# module.net
KiCad netlist of a schematic drawn in EAGLE
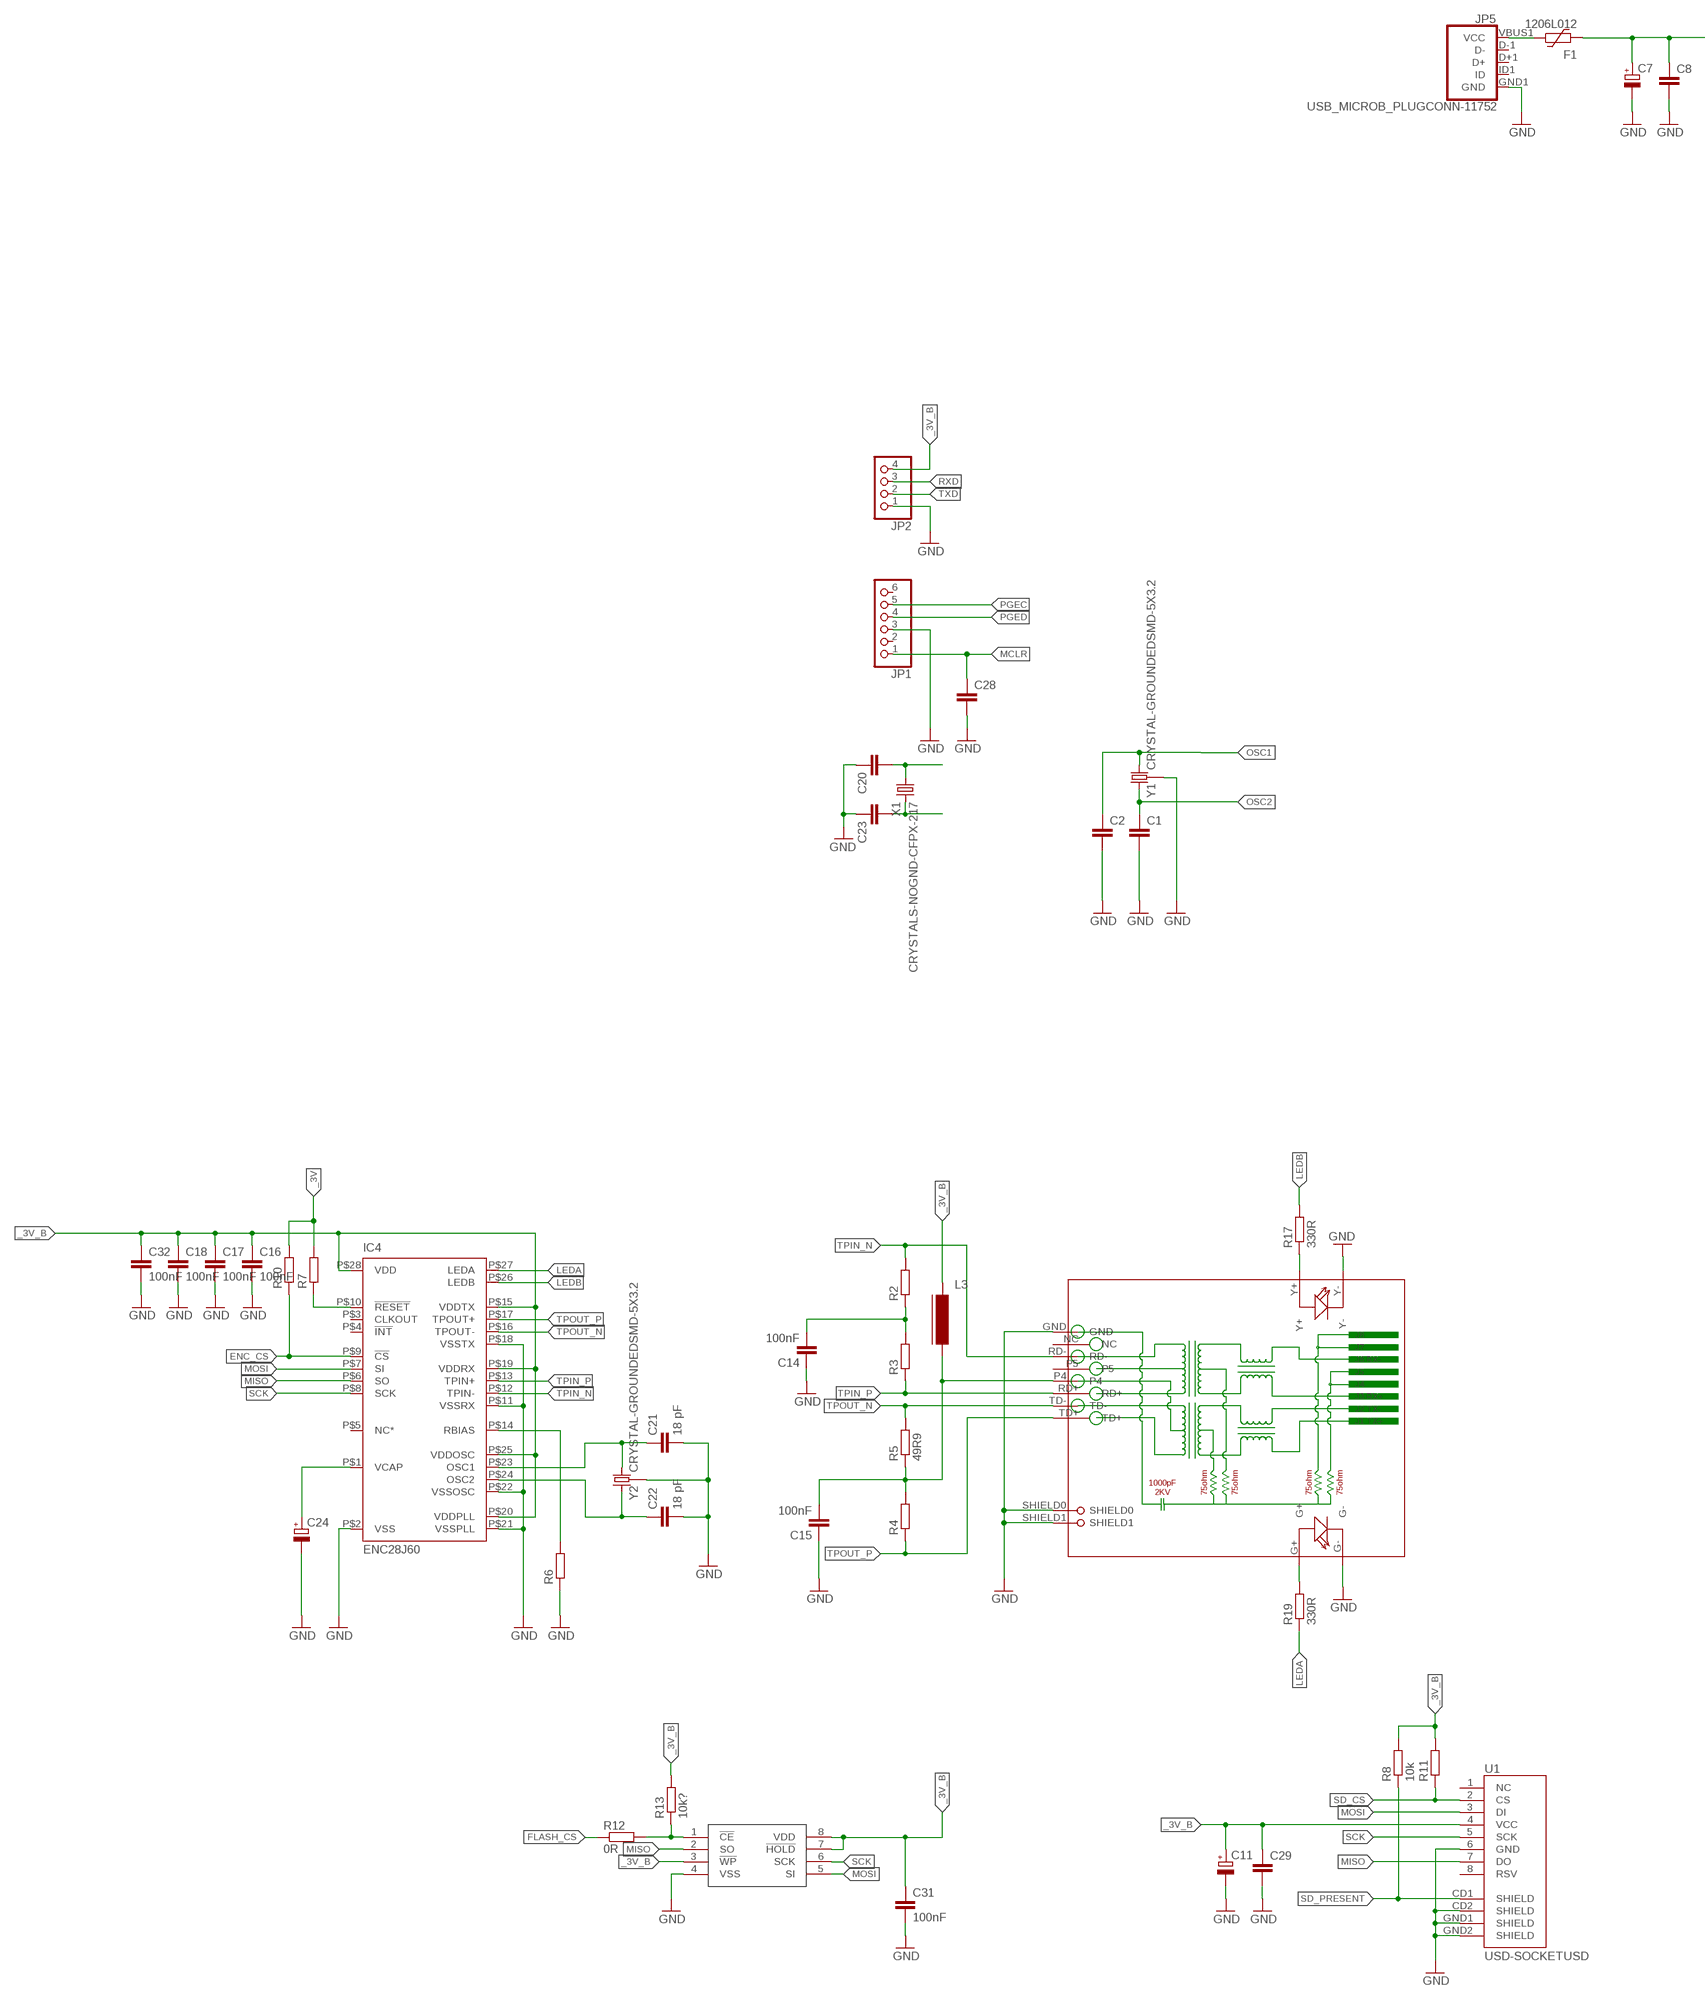
[diagram p0: schematic, sheet 1, part 1 of 2]
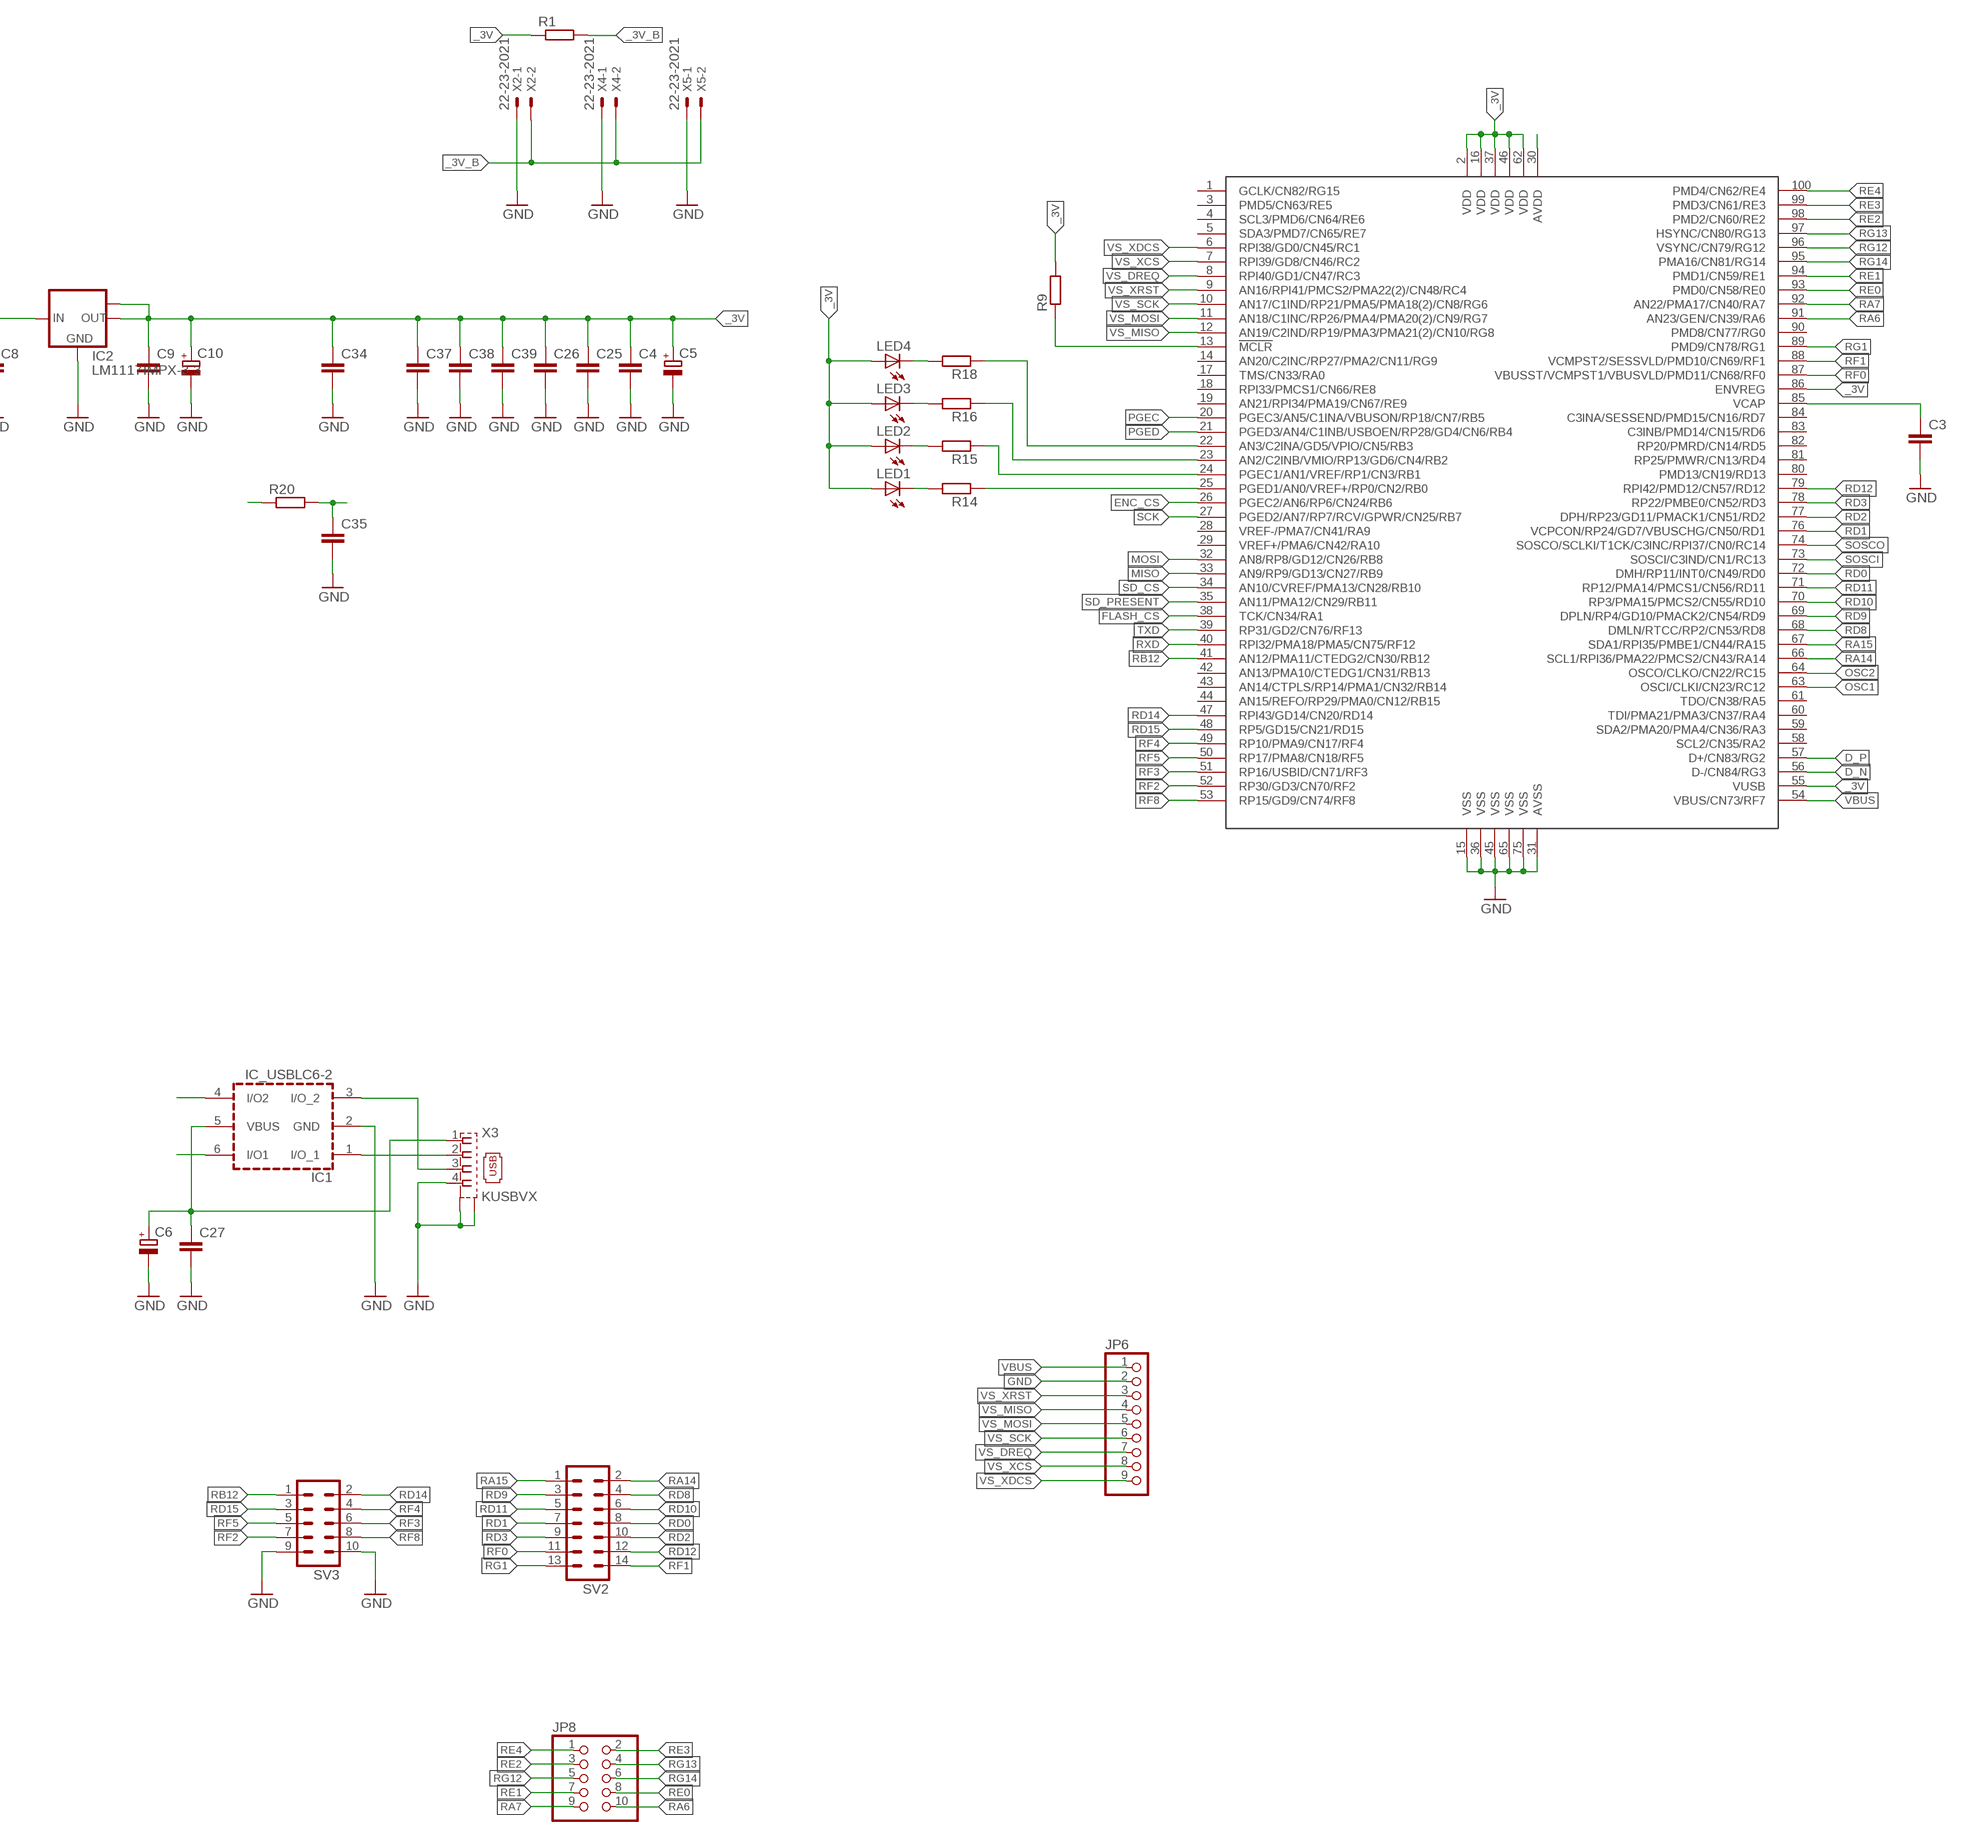
[diagram p1: schematic, sheet 1, part 2 of 2]

(export (version "E")
  (design (tool "Eeschema 10.0.6"))
  (components
    (comp (ref "C1")
      (value "C-EUC0603")
      (footprint "eagle-import:C0603")
      (libsource (lib "eagle-import") (part "C-EUC0603"))
    )
    (comp (ref "C2")
      (value "C-EUC0603")
      (footprint "eagle-import:C0603")
      (libsource (lib "eagle-import") (part "C-EUC0603"))
    )
    (comp (ref "C3")
      (value "C-EUC0603")
      (footprint "eagle-import:C0603")
      (libsource (lib "eagle-import") (part "C-EUC0603"))
    )
    (comp (ref "C4")
      (value "C-EUC0402")
      (footprint "eagle-import:C0402")
      (libsource (lib "eagle-import") (part "C-EUC0402"))
    )
    (comp (ref "C5")
      (value "CPOL-EUSMCA")
      (footprint "eagle-import:SMC_A")
      (libsource (lib "eagle-import") (part "CPOL-EUSMCA"))
    )
    (comp (ref "C6")
      (value "CPOL-EUSMCB")
      (footprint "eagle-import:SMC_B")
      (libsource (lib "eagle-import") (part "CPOL-EUSMCB"))
    )
    (comp (ref "C7")
      (value "CPOL-EUSMCB")
      (footprint "eagle-import:SMC_B")
      (libsource (lib "eagle-import") (part "CPOL-EUSMCB"))
    )
    (comp (ref "C8")
      (value "C-EUC0603")
      (footprint "eagle-import:C0603")
      (libsource (lib "eagle-import") (part "C-EUC0603"))
    )
    (comp (ref "C9")
      (value "C-EUC0603")
      (footprint "eagle-import:C0603")
      (libsource (lib "eagle-import") (part "C-EUC0603"))
    )
    (comp (ref "C10")
      (value "CPOL-EUSMCB")
      (footprint "eagle-import:SMC_B")
      (libsource (lib "eagle-import") (part "CPOL-EUSMCB"))
    )
    (comp (ref "C11")
      (value "CPOL-EUSMCA")
      (footprint "eagle-import:SMC_A")
      (libsource (lib "eagle-import") (part "CPOL-EUSMCA"))
    )
    (comp (ref "C14")
      (value "100nF")
      (footprint "eagle-import:C0603")
      (libsource (lib "eagle-import") (part "C-EUC0603"))
    )
    (comp (ref "C15")
      (value "100nF")
      (footprint "eagle-import:C0603")
      (libsource (lib "eagle-import") (part "C-EUC0603"))
    )
    (comp (ref "C16")
      (value "100nF")
      (footprint "eagle-import:C0402")
      (libsource (lib "eagle-import") (part "C-EUC0402"))
    )
    (comp (ref "C17")
      (value "100nF")
      (footprint "eagle-import:C0603")
      (libsource (lib "eagle-import") (part "C-EUC0603"))
    )
    (comp (ref "C18")
      (value "100nF")
      (footprint "eagle-import:C0603")
      (libsource (lib "eagle-import") (part "C-EUC0603"))
    )
    (comp (ref "C20")
      (value "C-EUC0603")
      (footprint "eagle-import:C0603")
      (libsource (lib "eagle-import") (part "C-EUC0603"))
    )
    (comp (ref "C21")
      (value "18 pF")
      (footprint "eagle-import:C0603")
      (libsource (lib "eagle-import") (part "C-EUC0603"))
    )
    (comp (ref "C22")
      (value "18 pF")
      (footprint "eagle-import:C0603")
      (libsource (lib "eagle-import") (part "C-EUC0603"))
    )
    (comp (ref "C23")
      (value "C-EUC0603")
      (footprint "eagle-import:C0603")
      (libsource (lib "eagle-import") (part "C-EUC0603"))
    )
    (comp (ref "C24")
      (value "CPOL-EUSMCA")
      (footprint "eagle-import:SMC_A")
      (libsource (lib "eagle-import") (part "CPOL-EUSMCA"))
    )
    (comp (ref "C25")
      (value "C-EUC0402")
      (footprint "eagle-import:C0402")
      (libsource (lib "eagle-import") (part "C-EUC0402"))
    )
    (comp (ref "C26")
      (value "C-EUC0402")
      (footprint "eagle-import:C0402")
      (libsource (lib "eagle-import") (part "C-EUC0402"))
    )
    (comp (ref "C27")
      (value "C-EUC0805")
      (footprint "eagle-import:C0805")
      (libsource (lib "eagle-import") (part "C-EUC0805"))
    )
    (comp (ref "C28")
      (value "C-EUC0603")
      (footprint "eagle-import:C0603")
      (libsource (lib "eagle-import") (part "C-EUC0603"))
    )
    (comp (ref "C29")
      (value "C-EUC0603")
      (footprint "eagle-import:C0603")
      (libsource (lib "eagle-import") (part "C-EUC0603"))
    )
    (comp (ref "C31")
      (value "100nF")
      (footprint "eagle-import:C0603")
      (libsource (lib "eagle-import") (part "C-EUC0603"))
    )
    (comp (ref "C32")
      (value "100nF")
      (footprint "eagle-import:C0402")
      (libsource (lib "eagle-import") (part "C-EUC0402"))
    )
    (comp (ref "C34")
      (value "C-EUC0402")
      (footprint "eagle-import:C0402")
      (libsource (lib "eagle-import") (part "C-EUC0402"))
    )
    (comp (ref "C35")
      (value "C-EUC0402")
      (footprint "eagle-import:C0402")
      (libsource (lib "eagle-import") (part "C-EUC0402"))
    )
    (comp (ref "C37")
      (value "C-EUC0402")
      (footprint "eagle-import:C0402")
      (libsource (lib "eagle-import") (part "C-EUC0402"))
    )
    (comp (ref "C38")
      (value "C-EUC0603")
      (footprint "eagle-import:C0603")
      (libsource (lib "eagle-import") (part "C-EUC0603"))
    )
    (comp (ref "C39")
      (value "C-EUC0402")
      (footprint "eagle-import:C0402")
      (libsource (lib "eagle-import") (part "C-EUC0402"))
    )
    (comp (ref "F1")
      (value "1206L012")
      (footprint "eagle-import:1206L")
      (fields (field (name "MF") "Littelfuse"))
      (libsource (lib "eagle-import") (part "?1206L012"))
    )
    (comp (ref "IC1")
      (value "IC_USBLC6-2")
      (footprint "eagle-import:SOT-23-6L")
      (libsource (lib "eagle-import") (part "IC_USBLC6-2"))
    )
    (comp (ref "IC2")
      (value "LM1117IMPX-3.3")
      (footprint "eagle-import:SOT223")
      (libsource (lib "eagle-import") (part "LM1117IMPX-3.3"))
    )
    (comp (ref "IC4")
      (value "ENC28J60")
      (footprint "eagle-import:TSSOP28W")
      (libsource (lib "eagle-import") (part "ENC28J60"))
    )
    (comp (ref "JP1")
      (value "PINHD-1X6")
      (footprint "eagle-import:1X06")
      (libsource (lib "eagle-import") (part "PINHD-1X6"))
    )
    (comp (ref "JP2")
      (value "PINHD-1X4")
      (footprint "eagle-import:1X04")
      (libsource (lib "eagle-import") (part "PINHD-1X4"))
    )
    (comp (ref "JP5")
      (value "USB_MICROB_PLUGCONN-11752")
      (footprint "eagle-import:USB-B-MICRO-SMD_V03")
      (libsource (lib "eagle-import") (part "USB_MICROB_PLUGCONN-11752"))
    )
    (comp (ref "JP6")
      (value "PINHD-1X9")
      (footprint "eagle-import:1X09")
      (libsource (lib "eagle-import") (part "PINHD-1X9"))
    )
    (comp (ref "JP8")
      (value "PINHD-2X5")
      (footprint "eagle-import:2X05")
      (libsource (lib "eagle-import") (part "PINHD-2X5"))
    )
    (comp (ref "L3")
      (value "FERRITE-0805")
      (footprint "eagle-import:FB805")
      (libsource (lib "eagle-import") (part "FERRITE-0805"))
    )
    (comp (ref "LED1")
      (value "LEDCHIP-LED0603")
      (footprint "eagle-import:CHIP-LED0603")
      (libsource (lib "eagle-import") (part "LEDCHIP-LED0603"))
    )
    (comp (ref "LED2")
      (value "LEDCHIP-LED0603")
      (footprint "eagle-import:CHIP-LED0603")
      (libsource (lib "eagle-import") (part "LEDCHIP-LED0603"))
    )
    (comp (ref "LED3")
      (value "LEDCHIP-LED0603")
      (footprint "eagle-import:CHIP-LED0603")
      (libsource (lib "eagle-import") (part "LEDCHIP-LED0603"))
    )
    (comp (ref "LED4")
      (value "LEDCHIP-LED0603")
      (footprint "eagle-import:CHIP-LED0603")
      (libsource (lib "eagle-import") (part "LEDCHIP-LED0603"))
    )
    (comp (ref "R1")
      (value "R-EU_R2010")
      (footprint "eagle-import:R2010")
      (libsource (lib "eagle-import") (part "R-EU_R2010"))
    )
    (comp (ref "R2")
      (value "R-EU_R0603")
      (footprint "eagle-import:R0603")
      (libsource (lib "eagle-import") (part "R-EU_R0603"))
    )
    (comp (ref "R3")
      (value "R-EU_R0603")
      (footprint "eagle-import:R0603")
      (libsource (lib "eagle-import") (part "R-EU_R0603"))
    )
    (comp (ref "R4")
      (value "R-EU_R0603")
      (footprint "eagle-import:R0603")
      (libsource (lib "eagle-import") (part "R-EU_R0603"))
    )
    (comp (ref "R5")
      (value "49R9")
      (footprint "eagle-import:R0603")
      (libsource (lib "eagle-import") (part "R-EU_R0603"))
    )
    (comp (ref "R6")
      (value "R-EU_R0805")
      (footprint "eagle-import:R0805")
      (libsource (lib "eagle-import") (part "R-EU_R0805"))
    )
    (comp (ref "R7")
      (value "R-EU_R0603")
      (footprint "eagle-import:R0603")
      (libsource (lib "eagle-import") (part "R-EU_R0603"))
    )
    (comp (ref "R8")
      (value "10k")
      (footprint "eagle-import:R0603")
      (libsource (lib "eagle-import") (part "R-EU_R0603"))
    )
    (comp (ref "R9")
      (value "R-EU_R0603")
      (footprint "eagle-import:R0603")
      (libsource (lib "eagle-import") (part "R-EU_R0603"))
    )
    (comp (ref "R10")
      (value "R-EU_R0603")
      (footprint "eagle-import:R0603")
      (libsource (lib "eagle-import") (part "R-EU_R0603"))
    )
    (comp (ref "R11")
      (value "R-EU_R0603")
      (footprint "eagle-import:R0603")
      (libsource (lib "eagle-import") (part "R-EU_R0603"))
    )
    (comp (ref "R12")
      (value "0R")
      (footprint "eagle-import:R0603")
      (libsource (lib "eagle-import") (part "R-EU_R0603"))
    )
    (comp (ref "R13")
      (value "10k?")
      (footprint "eagle-import:R0603")
      (libsource (lib "eagle-import") (part "R-EU_R0603"))
    )
    (comp (ref "R14")
      (value "R-EU_R0603")
      (footprint "eagle-import:R0603")
      (libsource (lib "eagle-import") (part "R-EU_R0603"))
    )
    (comp (ref "R15")
      (value "R-EU_R0603")
      (footprint "eagle-import:R0603")
      (libsource (lib "eagle-import") (part "R-EU_R0603"))
    )
    (comp (ref "R16")
      (value "R-EU_R0603")
      (footprint "eagle-import:R0603")
      (libsource (lib "eagle-import") (part "R-EU_R0603"))
    )
    (comp (ref "R17")
      (value "330R")
      (footprint "eagle-import:R1206")
      (libsource (lib "eagle-import") (part "R-EU_R1206"))
    )
    (comp (ref "R18")
      (value "R-EU_R0603")
      (footprint "eagle-import:R0603")
      (libsource (lib "eagle-import") (part "R-EU_R0603"))
    )
    (comp (ref "R19")
      (value "330R")
      (footprint "eagle-import:R1206")
      (libsource (lib "eagle-import") (part "R-EU_R1206"))
    )
    (comp (ref "R20")
      (value "R-EU_R0805")
      (footprint "eagle-import:R0805")
      (libsource (lib "eagle-import") (part "R-EU_R0805"))
    )
    (comp (ref "RJ1")
      (value "HR911105A")
      (footprint "eagle-import:HR911105A")
      (libsource (lib "eagle-import") (part "HR911105A"))
    )
    (comp (ref "SV2")
      (value "ML14L")
      (footprint "eagle-import:ML14L")
      (libsource (lib "eagle-import") (part "ML14L"))
    )
    (comp (ref "SV3")
      (value "ML10L")
      (footprint "eagle-import:ML10L")
      (libsource (lib "eagle-import") (part "ML10L"))
    )
    (comp (ref "U$1")
      (value "PIC24FJ256DA210SMALL")
      (footprint "eagle-import:TQFP100-12X12")
      (libsource (lib "eagle-import") (part "PIC24FJ256DA210SMALL"))
    )
    (comp (ref "U$2")
      (value "SST25VF016BSO8M")
      (footprint "eagle-import:SO-08M")
      (libsource (lib "eagle-import") (part "SST25VF016BSO8M"))
    )
    (comp (ref "U1")
      (value "USD-SOCKETUSD")
      (footprint "eagle-import:USD-SOCKET-PP")
      (libsource (lib "eagle-import") (part "USD-SOCKETUSD"))
    )
    (comp (ref "X1")
      (value "CRYSTALS-NOGND-CFPX-217")
      (footprint "eagle-import:3.2X1.5-2-PAD")
      (libsource (lib "eagle-import") (part "CRYSTALS-NOGND-CFPX-217"))
    )
    (comp (ref "X2")
      (value "22-23-2021")
      (footprint "eagle-import:22-23-2021")
      (fields (field (name "MF") "MOLEX"))
      (libsource (lib "eagle-import") (part "22-23-2021"))
    )
    (comp (ref "X3")
      (value "KUSBVX")
      (footprint "eagle-import:KUSBVX")
      (libsource (lib "eagle-import") (part "KUSBVX"))
    )
    (comp (ref "X4")
      (value "22-23-2021")
      (footprint "eagle-import:22-23-2021")
      (fields (field (name "MF") "MOLEX"))
      (libsource (lib "eagle-import") (part "22-23-2021"))
    )
    (comp (ref "X5")
      (value "22-23-2021")
      (footprint "eagle-import:22-23-2021")
      (fields (field (name "MF") "MOLEX"))
      (libsource (lib "eagle-import") (part "22-23-2021"))
    )
    (comp (ref "Y1")
      (value "CRYSTAL-GROUNDEDSMD-5X3.2")
      (footprint "eagle-import:CRYSTAL-SMD-5X3.2-4PAD")
      (libsource (lib "eagle-import") (part "CRYSTAL-GROUNDEDSMD-5X3.2"))
    )
    (comp (ref "Y2")
      (value "CRYSTAL-GROUNDEDSMD-5X3.2")
      (footprint "eagle-import:CRYSTAL-SMD-5X3.2-4PAD")
      (libsource (lib "eagle-import") (part "CRYSTAL-GROUNDEDSMD-5X3.2"))
    )
  )
  (nets
    (net (code "1") (name "/AVDD_3V") (class "Default")
      (node (ref "C35") (pin "1") (pinfunction "1_1") (pintype "passive"))
      (node (ref "R20") (pin "2") (pinfunction "2_2") (pintype "passive"))
      (node (ref "U$1") (pin "30") (pinfunction "AVDD_30") (pintype "bidirectional"))
    )
    (net (code "2") (name "D_N") (class "Default")
      (node (ref "IC1") (pin "6") (pinfunction "I/O1_6") (pintype "bidirectional"))
      (node (ref "U$1") (pin "56") (pinfunction "D-/CN84/RG3_56") (pintype "bidirectional"))
    )
    (net (code "3") (name "D_P") (class "Default")
      (node (ref "IC1") (pin "4") (pinfunction "I/O2_4") (pintype "bidirectional"))
      (node (ref "U$1") (pin "57") (pinfunction "D+/CN83/RG2_57") (pintype "bidirectional"))
    )
    (net (code "4") (name "ENC_CS") (class "Default")
      (node (ref "IC4") (pin "P$9") (pinfunction "~{CS}_P$9") (pintype "input"))
      (node (ref "R10") (pin "1") (pinfunction "1_1") (pintype "passive"))
      (node (ref "U$1") (pin "26") (pinfunction "PGEC2/AN6/RP6/CN24/RB6_26") (pintype "bidirectional"))
    )
    (net (code "5") (name "FLASH_CS") (class "Default")
      (node (ref "R12") (pin "1") (pinfunction "1_1") (pintype "passive"))
      (node (ref "U$1") (pin "38") (pinfunction "TCK/CN34/RA1_38") (pintype "bidirectional"))
    )
    (net (code "6") (name "GND") (class "Default")
      (node (ref "C1") (pin "2") (pinfunction "2_2") (pintype "passive"))
      (node (ref "C10") (pin "-") (pinfunction "-_-") (pintype "passive"))
      (node (ref "C11") (pin "-") (pinfunction "-_-") (pintype "passive"))
      (node (ref "C14") (pin "1") (pinfunction "1_1") (pintype "passive"))
      (node (ref "C15") (pin "1") (pinfunction "1_1") (pintype "passive"))
      (node (ref "C16") (pin "2") (pinfunction "2_2") (pintype "passive"))
      (node (ref "C17") (pin "2") (pinfunction "2_2") (pintype "passive"))
      (node (ref "C18") (pin "2") (pinfunction "2_2") (pintype "passive"))
      (node (ref "C2") (pin "2") (pinfunction "2_2") (pintype "passive"))
      (node (ref "C20") (pin "1") (pinfunction "1_1") (pintype "passive"))
      (node (ref "C21") (pin "2") (pinfunction "2_2") (pintype "passive"))
      (node (ref "C22") (pin "2") (pinfunction "2_2") (pintype "passive"))
      (node (ref "C23") (pin "1") (pinfunction "1_1") (pintype "passive"))
      (node (ref "C24") (pin "-") (pinfunction "-_-") (pintype "passive"))
      (node (ref "C25") (pin "2") (pinfunction "2_2") (pintype "passive"))
      (node (ref "C26") (pin "2") (pinfunction "2_2") (pintype "passive"))
      (node (ref "C27") (pin "2") (pinfunction "2_2") (pintype "passive"))
      (node (ref "C28") (pin "2") (pinfunction "2_2") (pintype "passive"))
      (node (ref "C29") (pin "2") (pinfunction "2_2") (pintype "passive"))
      (node (ref "C3") (pin "2") (pinfunction "2_2") (pintype "passive"))
      (node (ref "C31") (pin "2") (pinfunction "2_2") (pintype "passive"))
      (node (ref "C32") (pin "2") (pinfunction "2_2") (pintype "passive"))
      (node (ref "C34") (pin "2") (pinfunction "2_2") (pintype "passive"))
      (node (ref "C35") (pin "2") (pinfunction "2_2") (pintype "passive"))
      (node (ref "C37") (pin "2") (pinfunction "2_2") (pintype "passive"))
      (node (ref "C38") (pin "2") (pinfunction "2_2") (pintype "passive"))
      (node (ref "C39") (pin "2") (pinfunction "2_2") (pintype "passive"))
      (node (ref "C4") (pin "2") (pinfunction "2_2") (pintype "passive"))
      (node (ref "C5") (pin "-") (pinfunction "-_-") (pintype "passive"))
      (node (ref "C6") (pin "-") (pinfunction "-_-") (pintype "passive"))
      (node (ref "C7") (pin "-") (pinfunction "-_-") (pintype "passive"))
      (node (ref "C8") (pin "2") (pinfunction "2_2") (pintype "passive"))
      (node (ref "C9") (pin "2") (pinfunction "2_2") (pintype "passive"))
      (node (ref "IC1") (pin "2") (pinfunction "GND_2") (pintype "bidirectional"))
      (node (ref "IC2") (pin "1") (pinfunction "GND_1") (pintype "input"))
      (node (ref "IC4") (pin "P$11") (pinfunction "VSSRX_P$11") (pintype "input"))
      (node (ref "IC4") (pin "P$18") (pinfunction "VSSTX_P$18") (pintype "input"))
      (node (ref "IC4") (pin "P$2") (pinfunction "VSS_P$2") (pintype "input"))
      (node (ref "IC4") (pin "P$21") (pinfunction "VSSPLL_P$21") (pintype "input"))
      (node (ref "IC4") (pin "P$22") (pinfunction "VSSOSC_P$22") (pintype "input"))
      (node (ref "JP1") (pin "3") (pinfunction "3_3") (pintype "passive"))
      (node (ref "JP2") (pin "1") (pinfunction "1_1") (pintype "passive"))
      (node (ref "JP5") (pin "GND1") (pinfunction "GND_GND1") (pintype "bidirectional"))
      (node (ref "JP6") (pin "2") (pinfunction "2_2") (pintype "passive"))
      (node (ref "R6") (pin "1") (pinfunction "1_1") (pintype "passive"))
      (node (ref "RJ1") (pin "G-") (pinfunction "G-_G-") (pintype "bidirectional"))
      (node (ref "RJ1") (pin "GND") (pinfunction "GND_GND") (pintype "bidirectional"))
      (node (ref "RJ1") (pin "SHIELD0") (pinfunction "SHIELD0_SHIELD0") (pintype "bidirectional"))
      (node (ref "RJ1") (pin "SHIELD1") (pinfunction "SHIELD1_SHIELD1") (pintype "bidirectional"))
      (node (ref "RJ1") (pin "Y-") (pinfunction "Y-_Y-") (pintype "bidirectional"))
      (node (ref "SV3") (pin "10") (pinfunction "10_10") (pintype "passive"))
      (node (ref "SV3") (pin "9") (pinfunction "9_9") (pintype "passive"))
      (node (ref "U$1") (pin "15") (pinfunction "VSS_15") (pintype "bidirectional"))
      (node (ref "U$1") (pin "31") (pinfunction "AVSS_31") (pintype "bidirectional"))
      (node (ref "U$1") (pin "36") (pinfunction "VSS_36") (pintype "bidirectional"))
      (node (ref "U$1") (pin "45") (pinfunction "VSS_45") (pintype "bidirectional"))
      (node (ref "U$1") (pin "65") (pinfunction "VSS_65") (pintype "bidirectional"))
      (node (ref "U$1") (pin "75") (pinfunction "VSS_75") (pintype "bidirectional"))
      (node (ref "U$2") (pin "4") (pinfunction "VSS_4") (pintype "bidirectional"))
      (node (ref "U1") (pin "6") (pinfunction "GND_6") (pintype "bidirectional"))
      (node (ref "U1") (pin "CD2") (pinfunction "SHIELD_CD2") (pintype "bidirectional"))
      (node (ref "U1") (pin "GND1") (pinfunction "SHIELD_GND1") (pintype "bidirectional"))
      (node (ref "U1") (pin "GND2") (pinfunction "SHIELD_GND2") (pintype "bidirectional"))
      (node (ref "X2") (pin "1") (pinfunction "S_1") (pintype "passive"))
      (node (ref "X3") (pin "4") (pinfunction "4_4") (pintype "passive"))
      (node (ref "X3") (pin "M1") (pinfunction "S1_M1") (pintype "passive"))
      (node (ref "X3") (pin "M2") (pinfunction "S2_M2") (pintype "passive"))
      (node (ref "X4") (pin "1") (pinfunction "S_1") (pintype "passive"))
      (node (ref "X5") (pin "1") (pinfunction "S_1") (pintype "passive"))
      (node (ref "Y1") (pin "2") (pinfunction "3_2") (pintype "passive"))
      (node (ref "Y1") (pin "4") (pinfunction "3_4") (pintype "passive"))
      (node (ref "Y2") (pin "2") (pinfunction "3_2") (pintype "passive"))
      (node (ref "Y2") (pin "4") (pinfunction "3_4") (pintype "passive"))
    )
    (net (code "7") (name "LEDA") (class "Default")
      (node (ref "IC4") (pin "P$27") (pinfunction "LEDA_P$27") (pintype "output"))
      (node (ref "R19") (pin "1") (pinfunction "1_1") (pintype "passive"))
    )
    (net (code "8") (name "LEDB") (class "Default")
      (node (ref "IC4") (pin "P$26") (pinfunction "LEDB_P$26") (pintype "output"))
      (node (ref "R17") (pin "2") (pinfunction "2_2") (pintype "passive"))
    )
    (net (code "9") (name "MCLR") (class "Default")
      (node (ref "C28") (pin "1") (pinfunction "1_1") (pintype "passive"))
      (node (ref "JP1") (pin "1") (pinfunction "1_1") (pintype "passive"))
      (node (ref "R9") (pin "1") (pinfunction "1_1") (pintype "passive"))
      (node (ref "U$1") (pin "13") (pinfunction "~{MCLR}_13") (pintype "bidirectional"))
    )
    (net (code "10") (name "MISO") (class "Default")
      (node (ref "IC4") (pin "P$6") (pinfunction "SO_P$6") (pintype "output"))
      (node (ref "U$1") (pin "33") (pinfunction "AN9/RP9/GD13/CN27/RB9_33") (pintype "bidirectional"))
      (node (ref "U$2") (pin "2") (pinfunction "SO_2") (pintype "bidirectional"))
      (node (ref "U1") (pin "7") (pinfunction "DO_7") (pintype "bidirectional"))
    )
    (net (code "11") (name "MOSI") (class "Default")
      (node (ref "IC4") (pin "P$7") (pinfunction "SI_P$7") (pintype "input"))
      (node (ref "U$1") (pin "32") (pinfunction "AN8/RP8/GD12/CN26/RB8_32") (pintype "bidirectional"))
      (node (ref "U$2") (pin "5") (pinfunction "SI_5") (pintype "bidirectional"))
      (node (ref "U1") (pin "3") (pinfunction "DI_3") (pintype "bidirectional"))
    )
    (net (code "12") (name "Net-(C14-Pad2)") (class "Default")
      (node (ref "C14") (pin "2") (pinfunction "2_2") (pintype "passive"))
      (node (ref "R2") (pin "1") (pinfunction "1_1") (pintype "passive"))
      (node (ref "R3") (pin "2") (pinfunction "2_2") (pintype "passive"))
    )
    (net (code "13") (name "Net-(C15-Pad2)") (class "Default")
      (node (ref "C15") (pin "2") (pinfunction "2_2") (pintype "passive"))
      (node (ref "L3") (pin "2") (pinfunction "2_2") (pintype "passive"))
      (node (ref "R4") (pin "2") (pinfunction "2_2") (pintype "passive"))
      (node (ref "R5") (pin "1") (pinfunction "1_1") (pintype "passive"))
      (node (ref "RJ1") (pin "P4") (pinfunction "P4_P4") (pintype "bidirectional"))
    )
    (net (code "14") (name "Net-(IC1-I{slash}O_1)") (class "Default")
      (node (ref "IC1") (pin "1") (pinfunction "I/O_1_1") (pintype "bidirectional"))
      (node (ref "X3") (pin "2") (pinfunction "2_2") (pintype "passive"))
    )
    (net (code "15") (name "Net-(IC1-I{slash}O_2)") (class "Default")
      (node (ref "IC1") (pin "3") (pinfunction "I/O_2_3") (pintype "bidirectional"))
      (node (ref "X3") (pin "3") (pinfunction "3_3") (pintype "passive"))
    )
    (net (code "16") (name "Net-(IC4-OSC1)") (class "Default")
      (node (ref "C21") (pin "1") (pinfunction "1_1") (pintype "passive"))
      (node (ref "IC4") (pin "P$23") (pinfunction "OSC1_P$23") (pintype "input"))
      (node (ref "Y2") (pin "1") (pinfunction "2_1") (pintype "passive"))
    )
    (net (code "17") (name "Net-(IC4-OSC2)") (class "Default")
      (node (ref "C22") (pin "1") (pinfunction "1_1") (pintype "passive"))
      (node (ref "IC4") (pin "P$24") (pinfunction "OSC2_P$24") (pintype "output"))
      (node (ref "Y2") (pin "3") (pinfunction "1_3") (pintype "passive"))
    )
    (net (code "18") (name "Net-(IC4-RBIAS)") (class "Default")
      (node (ref "IC4") (pin "P$14") (pinfunction "RBIAS_P$14") (pintype "input"))
      (node (ref "R6") (pin "2") (pinfunction "2_2") (pintype "passive"))
    )
    (net (code "19") (name "Net-(IC4-VCAP)") (class "Default")
      (node (ref "C24") (pin "+") (pinfunction "+_+") (pintype "passive"))
      (node (ref "IC4") (pin "P$1") (pinfunction "VCAP_P$1") (pintype "input"))
    )
    (net (code "20") (name "Net-(IC4-~{RESET})") (class "Default")
      (node (ref "IC4") (pin "P$10") (pinfunction "~{RESET}_P$10") (pintype "input"))
      (node (ref "R7") (pin "1") (pinfunction "1_1") (pintype "passive"))
    )
    (net (code "21") (name "Net-(JP5-VCC)") (class "Default")
      (node (ref "F1") (pin "1") (pinfunction "1_1") (pintype "passive"))
      (node (ref "JP5") (pin "VBUS1") (pinfunction "VCC_VBUS1") (pintype "bidirectional"))
    )
    (net (code "22") (name "Net-(LED1-PadC)") (class "Default")
      (node (ref "LED1") (pin "C") (pinfunction "C_C") (pintype "passive"))
      (node (ref "R14") (pin "2") (pinfunction "2_2") (pintype "passive"))
    )
    (net (code "23") (name "Net-(LED2-PadC)") (class "Default")
      (node (ref "LED2") (pin "C") (pinfunction "C_C") (pintype "passive"))
      (node (ref "R15") (pin "2") (pinfunction "2_2") (pintype "passive"))
    )
    (net (code "24") (name "Net-(LED3-PadC)") (class "Default")
      (node (ref "LED3") (pin "C") (pinfunction "C_C") (pintype "passive"))
      (node (ref "R16") (pin "2") (pinfunction "2_2") (pintype "passive"))
    )
    (net (code "25") (name "Net-(LED4-PadC)") (class "Default")
      (node (ref "LED4") (pin "C") (pinfunction "C_C") (pintype "passive"))
      (node (ref "R18") (pin "2") (pinfunction "2_2") (pintype "passive"))
    )
    (net (code "26") (name "Net-(R17-Pad1)") (class "Default")
      (node (ref "R17") (pin "1") (pinfunction "1_1") (pintype "passive"))
      (node (ref "RJ1") (pin "Y+") (pinfunction "Y+_Y+") (pintype "bidirectional"))
    )
    (net (code "27") (name "Net-(R19-Pad2)") (class "Default")
      (node (ref "R19") (pin "2") (pinfunction "2_2") (pintype "passive"))
      (node (ref "RJ1") (pin "G+") (pinfunction "G+_G+") (pintype "bidirectional"))
    )
    (net (code "28") (name "Net-(U$1-AN2{slash}C2INB{slash}VMIO{slash}RP13{slash}GD6{slash}CN4{slash}RB2)") (class "Default")
      (node (ref "R16") (pin "1") (pinfunction "1_1") (pintype "passive"))
      (node (ref "U$1") (pin "23") (pinfunction "AN2/C2INB/VMIO/RP13/GD6/CN4/RB2_23") (pintype "bidirectional"))
    )
    (net (code "29") (name "Net-(U$1-AN3{slash}C2INA{slash}GD5{slash}VPIO{slash}CN5{slash}RB3)") (class "Default")
      (node (ref "R18") (pin "1") (pinfunction "1_1") (pintype "passive"))
      (node (ref "U$1") (pin "22") (pinfunction "AN3/C2INA/GD5/VPIO/CN5/RB3_22") (pintype "bidirectional"))
    )
    (net (code "30") (name "Net-(U$1-PGEC1{slash}AN1{slash}VREF{slash}RP1{slash}CN3{slash}RB1)") (class "Default")
      (node (ref "R15") (pin "1") (pinfunction "1_1") (pintype "passive"))
      (node (ref "U$1") (pin "24") (pinfunction "PGEC1/AN1/VREF/RP1/CN3/RB1_24") (pintype "bidirectional"))
    )
    (net (code "31") (name "Net-(U$1-PGED1{slash}AN0{slash}VREF+{slash}RP0{slash}CN2{slash}RB0)") (class "Default")
      (node (ref "R14") (pin "1") (pinfunction "1_1") (pintype "passive"))
      (node (ref "U$1") (pin "25") (pinfunction "PGED1/AN0/VREF+/RP0/CN2/RB0_25") (pintype "bidirectional"))
    )
    (net (code "32") (name "Net-(U$1-VCAP)") (class "Default")
      (node (ref "C3") (pin "1") (pinfunction "1_1") (pintype "passive"))
      (node (ref "U$1") (pin "85") (pinfunction "VCAP_85") (pintype "bidirectional"))
    )
    (net (code "33") (name "Net-(U$2-~{CE})") (class "Default")
      (node (ref "R12") (pin "2") (pinfunction "2_2") (pintype "passive"))
      (node (ref "R13") (pin "1") (pinfunction "1_1") (pintype "passive"))
      (node (ref "U$2") (pin "1") (pinfunction "~{CE}_1") (pintype "bidirectional"))
    )
    (net (code "34") (name "OSC1") (class "Default")
      (node (ref "C2") (pin "1") (pinfunction "1_1") (pintype "passive"))
      (node (ref "U$1") (pin "63") (pinfunction "OSCI/CLKI/CN23/RC12_63") (pintype "bidirectional"))
      (node (ref "Y1") (pin "1") (pinfunction "2_1") (pintype "passive"))
    )
    (net (code "35") (name "OSC2") (class "Default")
      (node (ref "C1") (pin "1") (pinfunction "1_1") (pintype "passive"))
      (node (ref "U$1") (pin "64") (pinfunction "OSCO/CLKO/CN22/RC15_64") (pintype "bidirectional"))
      (node (ref "Y1") (pin "3") (pinfunction "1_3") (pintype "passive"))
    )
    (net (code "36") (name "PGEC") (class "Default")
      (node (ref "JP1") (pin "5") (pinfunction "5_5") (pintype "passive"))
      (node (ref "U$1") (pin "20") (pinfunction "PGEC3/AN5/C1INA/VBUSON/RP18/CN7/RB5_20") (pintype "bidirectional"))
    )
    (net (code "37") (name "PGED") (class "Default")
      (node (ref "JP1") (pin "4") (pinfunction "4_4") (pintype "passive"))
      (node (ref "U$1") (pin "21") (pinfunction "PGED3/AN4/C1INB/USBOEN/RP28/GD4/CN6/RB4_21") (pintype "bidirectional"))
    )
    (net (code "38") (name "RA6") (class "Default")
      (node (ref "JP8") (pin "10") (pinfunction "10_10") (pintype "passive"))
      (node (ref "U$1") (pin "91") (pinfunction "AN23/GEN/CN39/RA6_91") (pintype "bidirectional"))
    )
    (net (code "39") (name "RA7") (class "Default")
      (node (ref "JP8") (pin "9") (pinfunction "9_9") (pintype "passive"))
      (node (ref "U$1") (pin "92") (pinfunction "AN22/PMA17/CN40/RA7_92") (pintype "bidirectional"))
    )
    (net (code "40") (name "RA14") (class "Default")
      (node (ref "SV2") (pin "2") (pinfunction "2_2") (pintype "passive"))
      (node (ref "U$1") (pin "66") (pinfunction "SCL1/RPI36/PMA22/PMCS2/CN43/RA14_66") (pintype "bidirectional"))
    )
    (net (code "41") (name "RA15") (class "Default")
      (node (ref "SV2") (pin "1") (pinfunction "1_1") (pintype "passive"))
      (node (ref "U$1") (pin "67") (pinfunction "SDA1/RPI35/PMBE1/CN44/RA15_67") (pintype "bidirectional"))
    )
    (net (code "42") (name "RB12") (class "Default")
      (node (ref "SV3") (pin "1") (pinfunction "1_1") (pintype "passive"))
      (node (ref "U$1") (pin "41") (pinfunction "AN12/PMA11/CTEDG2/CN30/RB12_41") (pintype "bidirectional"))
    )
    (net (code "43") (name "RD0") (class "Default")
      (node (ref "SV2") (pin "8") (pinfunction "8_8") (pintype "passive"))
      (node (ref "U$1") (pin "72") (pinfunction "DMH/RP11/INT0/CN49/RD0_72") (pintype "bidirectional"))
    )
    (net (code "44") (name "RD1") (class "Default")
      (node (ref "SV2") (pin "7") (pinfunction "7_7") (pintype "passive"))
      (node (ref "U$1") (pin "76") (pinfunction "VCPCON/RP24/GD7/VBUSCHG/CN50/RD1_76") (pintype "bidirectional"))
    )
    (net (code "45") (name "RD2") (class "Default")
      (node (ref "SV2") (pin "10") (pinfunction "10_10") (pintype "passive"))
      (node (ref "U$1") (pin "77") (pinfunction "DPH/RP23/GD11/PMACK1/CN51/RD2_77") (pintype "bidirectional"))
    )
    (net (code "46") (name "RD3") (class "Default")
      (node (ref "SV2") (pin "9") (pinfunction "9_9") (pintype "passive"))
      (node (ref "U$1") (pin "78") (pinfunction "RP22/PMBE0/CN52/RD3_78") (pintype "bidirectional"))
    )
    (net (code "47") (name "RD8") (class "Default")
      (node (ref "SV2") (pin "4") (pinfunction "4_4") (pintype "passive"))
      (node (ref "U$1") (pin "68") (pinfunction "DMLN/RTCC/RP2/CN53/RD8_68") (pintype "bidirectional"))
    )
    (net (code "48") (name "RD9") (class "Default")
      (node (ref "SV2") (pin "3") (pinfunction "3_3") (pintype "passive"))
      (node (ref "U$1") (pin "69") (pinfunction "DPLN/RP4/GD10/PMACK2/CN54/RD9_69") (pintype "bidirectional"))
    )
    (net (code "49") (name "RD10") (class "Default")
      (node (ref "SV2") (pin "6") (pinfunction "6_6") (pintype "passive"))
      (node (ref "U$1") (pin "70") (pinfunction "RP3/PMA15/PMCS2/CN55/RD10_70") (pintype "bidirectional"))
    )
    (net (code "50") (name "RD11") (class "Default")
      (node (ref "SV2") (pin "5") (pinfunction "5_5") (pintype "passive"))
      (node (ref "U$1") (pin "71") (pinfunction "RP12/PMA14/PMCS1/CN56/RD11_71") (pintype "bidirectional"))
    )
    (net (code "51") (name "RD12") (class "Default")
      (node (ref "SV2") (pin "12") (pinfunction "12_12") (pintype "passive"))
      (node (ref "U$1") (pin "79") (pinfunction "RPI42/PMD12/CN57/RD12_79") (pintype "bidirectional"))
    )
    (net (code "52") (name "RD14") (class "Default")
      (node (ref "SV3") (pin "2") (pinfunction "2_2") (pintype "passive"))
      (node (ref "U$1") (pin "47") (pinfunction "RPI43/GD14/CN20/RD14_47") (pintype "bidirectional"))
    )
    (net (code "53") (name "RD15") (class "Default")
      (node (ref "SV3") (pin "3") (pinfunction "3_3") (pintype "passive"))
      (node (ref "U$1") (pin "48") (pinfunction "RP5/GD15/CN21/RD15_48") (pintype "bidirectional"))
    )
    (net (code "54") (name "RE0") (class "Default")
      (node (ref "JP8") (pin "8") (pinfunction "8_8") (pintype "passive"))
      (node (ref "U$1") (pin "93") (pinfunction "PMD0/CN58/RE0_93") (pintype "bidirectional"))
    )
    (net (code "55") (name "RE1") (class "Default")
      (node (ref "JP8") (pin "7") (pinfunction "7_7") (pintype "passive"))
      (node (ref "U$1") (pin "94") (pinfunction "PMD1/CN59/RE1_94") (pintype "bidirectional"))
    )
    (net (code "56") (name "RE2") (class "Default")
      (node (ref "JP8") (pin "3") (pinfunction "3_3") (pintype "passive"))
      (node (ref "U$1") (pin "98") (pinfunction "PMD2/CN60/RE2_98") (pintype "bidirectional"))
    )
    (net (code "57") (name "RE3") (class "Default")
      (node (ref "JP8") (pin "2") (pinfunction "2_2") (pintype "passive"))
      (node (ref "U$1") (pin "99") (pinfunction "PMD3/CN61/RE3_99") (pintype "bidirectional"))
    )
    (net (code "58") (name "RE4") (class "Default")
      (node (ref "JP8") (pin "1") (pinfunction "1_1") (pintype "passive"))
      (node (ref "U$1") (pin "100") (pinfunction "PMD4/CN62/RE4_100") (pintype "bidirectional"))
    )
    (net (code "59") (name "RF0") (class "Default")
      (node (ref "SV2") (pin "11") (pinfunction "11_11") (pintype "passive"))
      (node (ref "U$1") (pin "87") (pinfunction "VBUSST/VCMPST1/VBUSVLD/PMD11/CN68/RF0_87") (pintype "bidirectional"))
    )
    (net (code "60") (name "RF1") (class "Default")
      (node (ref "SV2") (pin "14") (pinfunction "14_14") (pintype "passive"))
      (node (ref "U$1") (pin "88") (pinfunction "VCMPST2/SESSVLD/PMD10/CN69/RF1_88") (pintype "bidirectional"))
    )
    (net (code "61") (name "RF2") (class "Default")
      (node (ref "SV3") (pin "7") (pinfunction "7_7") (pintype "passive"))
      (node (ref "U$1") (pin "52") (pinfunction "RP30/GD3/CN70/RF2_52") (pintype "bidirectional"))
    )
    (net (code "62") (name "RF3") (class "Default")
      (node (ref "SV3") (pin "6") (pinfunction "6_6") (pintype "passive"))
      (node (ref "U$1") (pin "51") (pinfunction "RP16/USBID/CN71/RF3_51") (pintype "bidirectional"))
    )
    (net (code "63") (name "RF4") (class "Default")
      (node (ref "SV3") (pin "4") (pinfunction "4_4") (pintype "passive"))
      (node (ref "U$1") (pin "49") (pinfunction "RP10/PMA9/CN17/RF4_49") (pintype "bidirectional"))
    )
    (net (code "64") (name "RF5") (class "Default")
      (node (ref "SV3") (pin "5") (pinfunction "5_5") (pintype "passive"))
      (node (ref "U$1") (pin "50") (pinfunction "RP17/PMA8/CN18/RF5_50") (pintype "bidirectional"))
    )
    (net (code "65") (name "RF8") (class "Default")
      (node (ref "SV3") (pin "8") (pinfunction "8_8") (pintype "passive"))
      (node (ref "U$1") (pin "53") (pinfunction "RP15/GD9/CN74/RF8_53") (pintype "bidirectional"))
    )
    (net (code "66") (name "RG1") (class "Default")
      (node (ref "SV2") (pin "13") (pinfunction "13_13") (pintype "passive"))
      (node (ref "U$1") (pin "89") (pinfunction "PMD9/CN78/RG1_89") (pintype "bidirectional"))
    )
    (net (code "67") (name "RG12") (class "Default")
      (node (ref "JP8") (pin "5") (pinfunction "5_5") (pintype "passive"))
      (node (ref "U$1") (pin "96") (pinfunction "VSYNC/CN79/RG12_96") (pintype "bidirectional"))
    )
    (net (code "68") (name "RG13") (class "Default")
      (node (ref "JP8") (pin "4") (pinfunction "4_4") (pintype "passive"))
      (node (ref "U$1") (pin "97") (pinfunction "HSYNC/CN80/RG13_97") (pintype "bidirectional"))
    )
    (net (code "69") (name "RG14") (class "Default")
      (node (ref "JP8") (pin "6") (pinfunction "6_6") (pintype "passive"))
      (node (ref "U$1") (pin "95") (pinfunction "PMA16/CN81/RG14_95") (pintype "bidirectional"))
    )
    (net (code "70") (name "RXD") (class "Default")
      (node (ref "JP2") (pin "3") (pinfunction "3_3") (pintype "passive"))
      (node (ref "U$1") (pin "40") (pinfunction "RPI32/PMA18/PMA5/CN75/RF12_40") (pintype "bidirectional"))
    )
    (net (code "71") (name "SCK") (class "Default")
      (node (ref "IC4") (pin "P$8") (pinfunction "SCK_P$8") (pintype "input"))
      (node (ref "U$1") (pin "27") (pinfunction "PGED2/AN7/RP7/RCV/GPWR/CN25/RB7_27") (pintype "bidirectional"))
      (node (ref "U$2") (pin "6") (pinfunction "SCK_6") (pintype "bidirectional"))
      (node (ref "U1") (pin "5") (pinfunction "SCK_5") (pintype "bidirectional"))
    )
    (net (code "72") (name "SD_CS") (class "Default")
      (node (ref "R11") (pin "1") (pinfunction "1_1") (pintype "passive"))
      (node (ref "U$1") (pin "34") (pinfunction "AN10/CVREF/PMA13/CN28/RB10_34") (pintype "bidirectional"))
      (node (ref "U1") (pin "2") (pinfunction "CS_2") (pintype "bidirectional"))
    )
    (net (code "73") (name "SD_PRESENT") (class "Default")
      (node (ref "R8") (pin "1") (pinfunction "1_1") (pintype "passive"))
      (node (ref "U$1") (pin "35") (pinfunction "AN11/PMA12/CN29/RB11_35") (pintype "bidirectional"))
      (node (ref "U1") (pin "CD1") (pinfunction "SHIELD_CD1") (pintype "bidirectional"))
    )
    (net (code "74") (name "SOSCI") (class "Default")
      (node (ref "C20") (pin "2") (pinfunction "2_2") (pintype "passive"))
      (node (ref "U$1") (pin "73") (pinfunction "SOSCI/C3IND/CN1/RC13_73") (pintype "bidirectional"))
      (node (ref "X1") (pin "1") (pinfunction "1_1") (pintype "passive"))
    )
    (net (code "75") (name "SOSCO") (class "Default")
      (node (ref "C23") (pin "2") (pinfunction "2_2") (pintype "passive"))
      (node (ref "U$1") (pin "74") (pinfunction "SOSCO/SCLKI/T1CK/C3INC/RPI37/CN0/RC14_74") (pintype "bidirectional"))
      (node (ref "X1") (pin "2") (pinfunction "2_2") (pintype "passive"))
    )
    (net (code "76") (name "TPIN_N") (class "Default")
      (node (ref "IC4") (pin "P$12") (pinfunction "TPIN-_P$12") (pintype "input"))
      (node (ref "R2") (pin "2") (pinfunction "2_2") (pintype "passive"))
      (node (ref "RJ1") (pin "RD-") (pinfunction "RD-_RD-") (pintype "bidirectional"))
    )
    (net (code "77") (name "TPIN_P") (class "Default")
      (node (ref "IC4") (pin "P$13") (pinfunction "TPIN+_P$13") (pintype "input"))
      (node (ref "R3") (pin "1") (pinfunction "1_1") (pintype "passive"))
      (node (ref "RJ1") (pin "RD+") (pinfunction "RD+_RD+") (pintype "bidirectional"))
    )
    (net (code "78") (name "TPOUT_N") (class "Default")
      (node (ref "IC4") (pin "P$16") (pinfunction "TPOUT-_P$16") (pintype "output"))
      (node (ref "R5") (pin "2") (pinfunction "2_2") (pintype "passive"))
      (node (ref "RJ1") (pin "TD-") (pinfunction "TD-_TD-") (pintype "bidirectional"))
    )
    (net (code "79") (name "TPOUT_P") (class "Default")
      (node (ref "IC4") (pin "P$17") (pinfunction "TPOUT+_P$17") (pintype "output"))
      (node (ref "R4") (pin "1") (pinfunction "1_1") (pintype "passive"))
      (node (ref "RJ1") (pin "TD+") (pinfunction "TD+_TD+") (pintype "bidirectional"))
    )
    (net (code "80") (name "TXD") (class "Default")
      (node (ref "JP2") (pin "2") (pinfunction "2_2") (pintype "passive"))
      (node (ref "U$1") (pin "39") (pinfunction "RP31/GD2/CN76/RF13_39") (pintype "bidirectional"))
    )
    (net (code "81") (name "VBUS") (class "Default")
      (node (ref "C27") (pin "1") (pinfunction "1_1") (pintype "passive"))
      (node (ref "C6") (pin "+") (pinfunction "+_+") (pintype "passive"))
      (node (ref "C7") (pin "+") (pinfunction "+_+") (pintype "passive"))
      (node (ref "C8") (pin "1") (pinfunction "1_1") (pintype "passive"))
      (node (ref "F1") (pin "2") (pinfunction "2_2") (pintype "passive"))
      (node (ref "IC1") (pin "5") (pinfunction "VBUS_5") (pintype "bidirectional"))
      (node (ref "IC2") (pin "3") (pinfunction "IN_3") (pintype "input"))
      (node (ref "JP6") (pin "1") (pinfunction "1_1") (pintype "passive"))
      (node (ref "U$1") (pin "54") (pinfunction "VBUS/CN73/RF7_54") (pintype "bidirectional"))
      (node (ref "X3") (pin "1") (pinfunction "1_1") (pintype "passive"))
    )
    (net (code "82") (name "VS_DREQ") (class "Default")
      (node (ref "JP6") (pin "7") (pinfunction "7_7") (pintype "passive"))
      (node (ref "U$1") (pin "8") (pinfunction "RPI40/GD1/CN47/RC3_8") (pintype "bidirectional"))
    )
    (net (code "83") (name "VS_MISO") (class "Default")
      (node (ref "JP6") (pin "4") (pinfunction "4_4") (pintype "passive"))
      (node (ref "U$1") (pin "12") (pinfunction "AN19/C2IND/RP19/PMA3/PMA21(2)/CN10/RG8_12") (pintype "bidirectional"))
    )
    (net (code "84") (name "VS_MOSI") (class "Default")
      (node (ref "JP6") (pin "5") (pinfunction "5_5") (pintype "passive"))
      (node (ref "U$1") (pin "11") (pinfunction "AN18/C1INC/RP26/PMA4/PMA20(2)/CN9/RG7_11") (pintype "bidirectional"))
    )
    (net (code "85") (name "VS_SCK") (class "Default")
      (node (ref "JP6") (pin "6") (pinfunction "6_6") (pintype "passive"))
      (node (ref "U$1") (pin "10") (pinfunction "AN17/C1IND/RP21/PMA5/PMA18(2)/CN8/RG6_10") (pintype "bidirectional"))
    )
    (net (code "86") (name "VS_XCS") (class "Default")
      (node (ref "JP6") (pin "8") (pinfunction "8_8") (pintype "passive"))
      (node (ref "U$1") (pin "7") (pinfunction "RPI39/GD8/CN46/RC2_7") (pintype "bidirectional"))
    )
    (net (code "87") (name "VS_XDCS") (class "Default")
      (node (ref "JP6") (pin "9") (pinfunction "9_9") (pintype "passive"))
      (node (ref "U$1") (pin "6") (pinfunction "RPI38/GD0/CN45/RC1_6") (pintype "bidirectional"))
    )
    (net (code "88") (name "VS_XRST") (class "Default")
      (node (ref "JP6") (pin "3") (pinfunction "3_3") (pintype "passive"))
      (node (ref "U$1") (pin "9") (pinfunction "AN16/RPI41/PMCS2/PMA22(2)/CN48/RC4_9") (pintype "bidirectional"))
    )
    (net (code "89") (name "_3V") (class "Default")
      (node (ref "C10") (pin "+") (pinfunction "+_+") (pintype "passive"))
      (node (ref "C25") (pin "1") (pinfunction "1_1") (pintype "passive"))
      (node (ref "C26") (pin "1") (pinfunction "1_1") (pintype "passive"))
      (node (ref "C34") (pin "1") (pinfunction "1_1") (pintype "passive"))
      (node (ref "C37") (pin "1") (pinfunction "1_1") (pintype "passive"))
      (node (ref "C38") (pin "1") (pinfunction "1_1") (pintype "passive"))
      (node (ref "C39") (pin "1") (pinfunction "1_1") (pintype "passive"))
      (node (ref "C4") (pin "1") (pinfunction "1_1") (pintype "passive"))
      (node (ref "C5") (pin "+") (pinfunction "+_+") (pintype "passive"))
      (node (ref "C9") (pin "1") (pinfunction "1_1") (pintype "passive"))
      (node (ref "IC2") (pin "2") (pinfunction "OUT_2") (pintype "passive"))
      (node (ref "IC2") (pin "TAB") (pinfunction "OUT1_TAB") (pintype "passive"))
      (node (ref "LED1") (pin "A") (pinfunction "A_A") (pintype "passive"))
      (node (ref "LED2") (pin "A") (pinfunction "A_A") (pintype "passive"))
      (node (ref "LED3") (pin "A") (pinfunction "A_A") (pintype "passive"))
      (node (ref "LED4") (pin "A") (pinfunction "A_A") (pintype "passive"))
      (node (ref "R1") (pin "1") (pinfunction "1_1") (pintype "passive"))
      (node (ref "R10") (pin "2") (pinfunction "2_2") (pintype "passive"))
      (node (ref "R20") (pin "1") (pinfunction "1_1") (pintype "passive"))
      (node (ref "R7") (pin "2") (pinfunction "2_2") (pintype "passive"))
      (node (ref "R9") (pin "2") (pinfunction "2_2") (pintype "passive"))
      (node (ref "U$1") (pin "16") (pinfunction "VDD_16") (pintype "bidirectional"))
      (node (ref "U$1") (pin "2") (pinfunction "VDD_2") (pintype "bidirectional"))
      (node (ref "U$1") (pin "37") (pinfunction "VDD_37") (pintype "bidirectional"))
      (node (ref "U$1") (pin "46") (pinfunction "VDD_46") (pintype "bidirectional"))
      (node (ref "U$1") (pin "55") (pinfunction "VUSB_55") (pintype "bidirectional"))
      (node (ref "U$1") (pin "62") (pinfunction "VDD_62") (pintype "bidirectional"))
      (node (ref "U$1") (pin "86") (pinfunction "ENVREG_86") (pintype "bidirectional"))
    )
    (net (code "90") (name "_3V_B") (class "Default")
      (node (ref "C11") (pin "+") (pinfunction "+_+") (pintype "passive"))
      (node (ref "C16") (pin "1") (pinfunction "1_1") (pintype "passive"))
      (node (ref "C17") (pin "1") (pinfunction "1_1") (pintype "passive"))
      (node (ref "C18") (pin "1") (pinfunction "1_1") (pintype "passive"))
      (node (ref "C29") (pin "1") (pinfunction "1_1") (pintype "passive"))
      (node (ref "C31") (pin "1") (pinfunction "1_1") (pintype "passive"))
      (node (ref "C32") (pin "1") (pinfunction "1_1") (pintype "passive"))
      (node (ref "IC4") (pin "P$15") (pinfunction "VDDTX_P$15") (pintype "input"))
      (node (ref "IC4") (pin "P$19") (pinfunction "VDDRX_P$19") (pintype "input"))
      (node (ref "IC4") (pin "P$20") (pinfunction "VDDPLL_P$20") (pintype "input"))
      (node (ref "IC4") (pin "P$25") (pinfunction "VDDOSC_P$25") (pintype "input"))
      (node (ref "IC4") (pin "P$28") (pinfunction "VDD_P$28") (pintype "input"))
      (node (ref "JP2") (pin "4") (pinfunction "4_4") (pintype "passive"))
      (node (ref "L3") (pin "1") (pinfunction "1_1") (pintype "passive"))
      (node (ref "R1") (pin "2") (pinfunction "2_2") (pintype "passive"))
      (node (ref "R11") (pin "2") (pinfunction "2_2") (pintype "passive"))
      (node (ref "R13") (pin "2") (pinfunction "2_2") (pintype "passive"))
      (node (ref "R8") (pin "2") (pinfunction "2_2") (pintype "passive"))
      (node (ref "U$2") (pin "3") (pinfunction "~{WP}_3") (pintype "bidirectional"))
      (node (ref "U$2") (pin "7") (pinfunction "~{HOLD}_7") (pintype "bidirectional"))
      (node (ref "U$2") (pin "8") (pinfunction "VDD_8") (pintype "bidirectional"))
      (node (ref "U1") (pin "4") (pinfunction "VCC_4") (pintype "bidirectional"))
      (node (ref "X2") (pin "2") (pinfunction "S_2") (pintype "passive"))
      (node (ref "X4") (pin "2") (pinfunction "S_2") (pintype "passive"))
      (node (ref "X5") (pin "2") (pinfunction "S_2") (pintype "passive"))
    )
    (net (code "91") (name "unconnected-(IC4-CLKOUT-PadP$3)") (class "Default")
      (node (ref "IC4") (pin "P$3") (pinfunction "CLKOUT_P$3") (pintype "output"))
    )
    (net (code "92") (name "unconnected-(IC4-NC*-PadP$5)") (class "Default")
      (node (ref "IC4") (pin "P$5") (pinfunction "NC*_P$5") (pintype "output"))
    )
    (net (code "93") (name "unconnected-(IC4-~{INT}-PadP$4)") (class "Default")
      (node (ref "IC4") (pin "P$4") (pinfunction "~{INT}_P$4") (pintype "output"))
    )
    (net (code "94") (name "unconnected-(JP1-Pad2)") (class "Default")
      (node (ref "JP1") (pin "2") (pinfunction "2_2") (pintype "passive"))
    )
    (net (code "95") (name "unconnected-(JP1-Pad6)") (class "Default")
      (node (ref "JP1") (pin "6") (pinfunction "6_6") (pintype "passive"))
    )
    (net (code "96") (name "unconnected-(JP5-D+-PadD+1)") (class "Default")
      (node (ref "JP5") (pin "D+1") (pinfunction "D+_D+1") (pintype "bidirectional"))
    )
    (net (code "97") (name "unconnected-(JP5-D--PadD-1)") (class "Default")
      (node (ref "JP5") (pin "D-1") (pinfunction "D-_D-1") (pintype "bidirectional"))
    )
    (net (code "98") (name "unconnected-(JP5-ID-PadID1)") (class "Default")
      (node (ref "JP5") (pin "ID1") (pinfunction "ID_ID1") (pintype "bidirectional"))
    )
    (net (code "99") (name "unconnected-(RJ1-PadNC)") (class "Default")
      (node (ref "RJ1") (pin "NC") (pinfunction "NC_NC") (pintype "bidirectional"))
    )
    (net (code "100") (name "unconnected-(RJ1-PadP5)") (class "Default")
      (node (ref "RJ1") (pin "P5") (pinfunction "P5_P5") (pintype "bidirectional"))
    )
    (net (code "101") (name "unconnected-(U$1-AN13{slash}PMA10{slash}CTEDG1{slash}CN31{slash}RB13-Pad42)") (class "Default")
      (node (ref "U$1") (pin "42") (pinfunction "AN13/PMA10/CTEDG1/CN31/RB13_42") (pintype "bidirectional"))
    )
    (net (code "102") (name "unconnected-(U$1-AN14{slash}CTPLS{slash}RP14{slash}PMA1{slash}CN32{slash}RB14-Pad43)") (class "Default")
      (node (ref "U$1") (pin "43") (pinfunction "AN14/CTPLS/RP14/PMA1/CN32/RB14_43") (pintype "bidirectional"))
    )
    (net (code "103") (name "unconnected-(U$1-AN15{slash}REFO{slash}RP29{slash}PMA0{slash}CN12{slash}RB15-Pad44)") (class "Default")
      (node (ref "U$1") (pin "44") (pinfunction "AN15/REFO/RP29/PMA0/CN12/RB15_44") (pintype "bidirectional"))
    )
    (net (code "104") (name "unconnected-(U$1-AN20{slash}C2INC{slash}RP27{slash}PMA2{slash}CN11{slash}RG9-Pad14)") (class "Default")
      (node (ref "U$1") (pin "14") (pinfunction "AN20/C2INC/RP27/PMA2/CN11/RG9_14") (pintype "bidirectional"))
    )
    (net (code "105") (name "unconnected-(U$1-AN21{slash}RPI34{slash}PMA19{slash}CN67{slash}RE9-Pad19)") (class "Default")
      (node (ref "U$1") (pin "19") (pinfunction "AN21/RPI34/PMA19/CN67/RE9_19") (pintype "bidirectional"))
    )
    (net (code "106") (name "unconnected-(U$1-C3INA{slash}SESSEND{slash}PMD15{slash}CN16{slash}RD7-Pad84)") (class "Default")
      (node (ref "U$1") (pin "84") (pinfunction "C3INA/SESSEND/PMD15/CN16/RD7_84") (pintype "bidirectional"))
    )
    (net (code "107") (name "unconnected-(U$1-C3INB{slash}PMD14{slash}CN15{slash}RD6-Pad83)") (class "Default")
      (node (ref "U$1") (pin "83") (pinfunction "C3INB/PMD14/CN15/RD6_83") (pintype "bidirectional"))
    )
    (net (code "108") (name "unconnected-(U$1-GCLK{slash}CN82{slash}RG15-Pad1)") (class "Default")
      (node (ref "U$1") (pin "1") (pinfunction "GCLK/CN82/RG15_1") (pintype "bidirectional"))
    )
    (net (code "109") (name "unconnected-(U$1-PMD5{slash}CN63{slash}RE5-Pad3)") (class "Default")
      (node (ref "U$1") (pin "3") (pinfunction "PMD5/CN63/RE5_3") (pintype "bidirectional"))
    )
    (net (code "110") (name "unconnected-(U$1-PMD8{slash}CN77{slash}RG0-Pad90)") (class "Default")
      (node (ref "U$1") (pin "90") (pinfunction "PMD8/CN77/RG0_90") (pintype "bidirectional"))
    )
    (net (code "111") (name "unconnected-(U$1-PMD13{slash}CN19{slash}RD13-Pad80)") (class "Default")
      (node (ref "U$1") (pin "80") (pinfunction "PMD13/CN19/RD13_80") (pintype "bidirectional"))
    )
    (net (code "112") (name "unconnected-(U$1-RP20{slash}PMRD{slash}CN14{slash}RD5-Pad82)") (class "Default")
      (node (ref "U$1") (pin "82") (pinfunction "RP20/PMRD/CN14/RD5_82") (pintype "bidirectional"))
    )
    (net (code "113") (name "unconnected-(U$1-RP25{slash}PMWR{slash}CN13{slash}RD4-Pad81)") (class "Default")
      (node (ref "U$1") (pin "81") (pinfunction "RP25/PMWR/CN13/RD4_81") (pintype "bidirectional"))
    )
    (net (code "114") (name "unconnected-(U$1-RPI33{slash}PMCS1{slash}CN66{slash}RE8-Pad18)") (class "Default")
      (node (ref "U$1") (pin "18") (pinfunction "RPI33/PMCS1/CN66/RE8_18") (pintype "bidirectional"))
    )
    (net (code "115") (name "unconnected-(U$1-SCL2{slash}CN35{slash}RA2-Pad58)") (class "Default")
      (node (ref "U$1") (pin "58") (pinfunction "SCL2/CN35/RA2_58") (pintype "bidirectional"))
    )
    (net (code "116") (name "unconnected-(U$1-SCL3{slash}PMD6{slash}CN64{slash}RE6-Pad4)") (class "Default")
      (node (ref "U$1") (pin "4") (pinfunction "SCL3/PMD6/CN64/RE6_4") (pintype "bidirectional"))
    )
    (net (code "117") (name "unconnected-(U$1-SDA2{slash}PMA20{slash}PMA4{slash}CN36{slash}RA3-Pad59)") (class "Default")
      (node (ref "U$1") (pin "59") (pinfunction "SDA2/PMA20/PMA4/CN36/RA3_59") (pintype "bidirectional"))
    )
    (net (code "118") (name "unconnected-(U$1-SDA3{slash}PMD7{slash}CN65{slash}RE7-Pad5)") (class "Default")
      (node (ref "U$1") (pin "5") (pinfunction "SDA3/PMD7/CN65/RE7_5") (pintype "bidirectional"))
    )
    (net (code "119") (name "unconnected-(U$1-TDI{slash}PMA21{slash}PMA3{slash}CN37{slash}RA4-Pad60)") (class "Default")
      (node (ref "U$1") (pin "60") (pinfunction "TDI/PMA21/PMA3/CN37/RA4_60") (pintype "bidirectional"))
    )
    (net (code "120") (name "unconnected-(U$1-TDO{slash}CN38{slash}RA5-Pad61)") (class "Default")
      (node (ref "U$1") (pin "61") (pinfunction "TDO/CN38/RA5_61") (pintype "bidirectional"))
    )
    (net (code "121") (name "unconnected-(U$1-TMS{slash}CN33{slash}RA0-Pad17)") (class "Default")
      (node (ref "U$1") (pin "17") (pinfunction "TMS/CN33/RA0_17") (pintype "bidirectional"))
    )
    (net (code "122") (name "unconnected-(U$1-VREF+{slash}PMA6{slash}CN42{slash}RA10-Pad29)") (class "Default")
      (node (ref "U$1") (pin "29") (pinfunction "VREF+/PMA6/CN42/RA10_29") (pintype "bidirectional"))
    )
    (net (code "123") (name "unconnected-(U$1-VREF-{slash}PMA7{slash}CN41{slash}RA9-Pad28)") (class "Default")
      (node (ref "U$1") (pin "28") (pinfunction "VREF-/PMA7/CN41/RA9_28") (pintype "bidirectional"))
    )
    (net (code "124") (name "unconnected-(U1-NC-Pad1)") (class "Default")
      (node (ref "U1") (pin "1") (pinfunction "NC_1") (pintype "bidirectional"))
    )
    (net (code "125") (name "unconnected-(U1-RSV-Pad8)") (class "Default")
      (node (ref "U1") (pin "8") (pinfunction "RSV_8") (pintype "bidirectional"))
    )
  )
)
